# QRE1113_Digital_v10.net
KiCad netlist of a schematic drawn in EAGLE
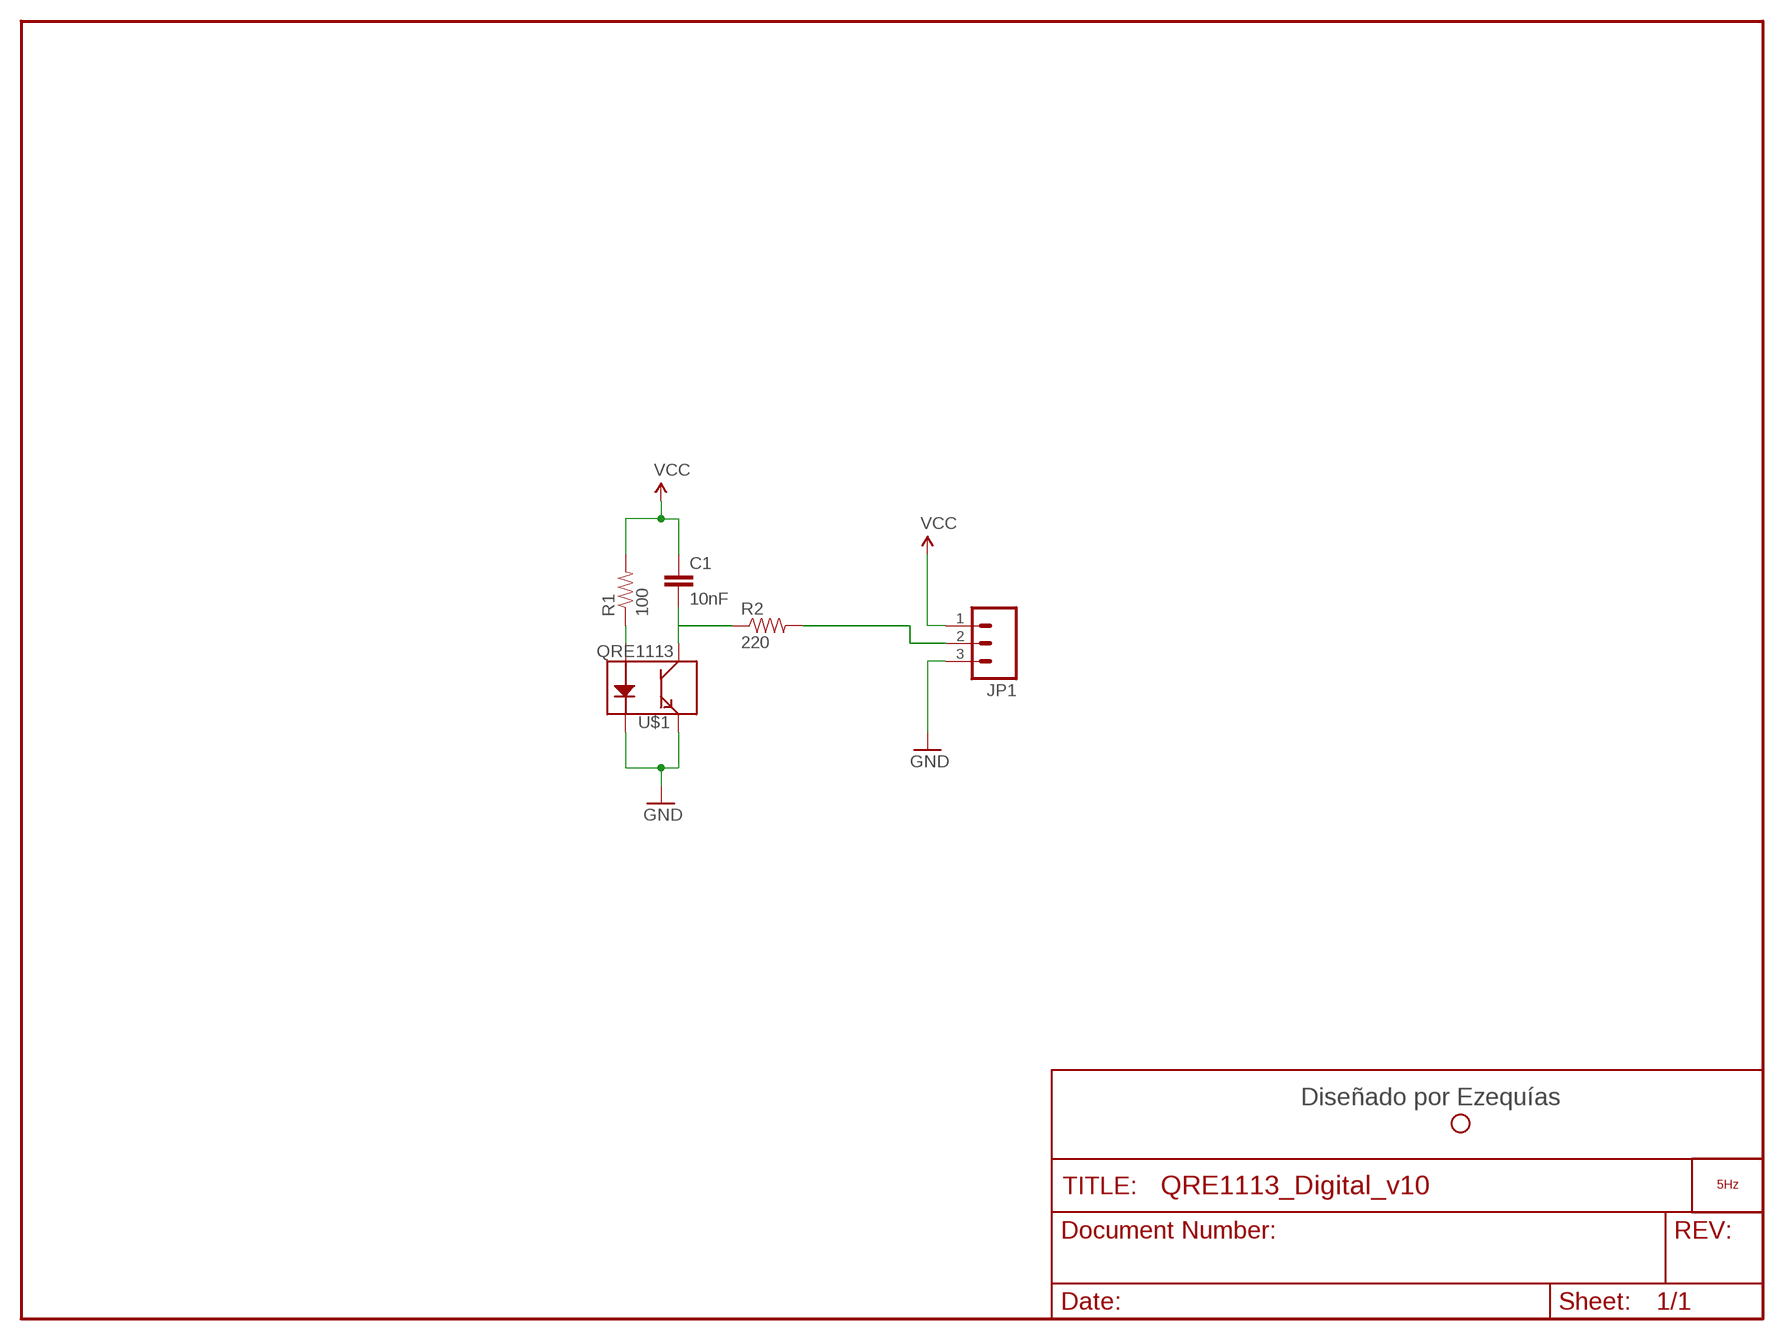
[diagram p0: schematic, sheet 1]

(export (version "E")
  (design (tool "Eeschema 10.0.6"))
  (components
    (comp (ref "C1")
      (value "10nF")
      (footprint "eagle-import:0603-CAP")
      (libsource (lib "eagle-import") (part "CAP0603-CAP"))
    )
    (comp (ref "JP1")
      (value "M03PTH")
      (footprint "eagle-import:1X03")
      (libsource (lib "eagle-import") (part "M03PTH"))
    )
    (comp (ref "JP2")
      (value "STAND-OFF")
      (footprint "eagle-import:STAND-OFF")
      (libsource (lib "eagle-import") (part "STAND-OFF"))
    )
    (comp (ref "LOGO1")
      (value "LOGO_5HZ_CIRC_5MM")
      (footprint "eagle-import:5HZ_LOGO_CIRC_5MM")
      (libsource (lib "eagle-import") (part "LOGO_5HZ_CIRC_5MM"))
    )
    (comp (ref "R1")
      (value "100")
      (footprint "eagle-import:0603-RES")
      (libsource (lib "eagle-import") (part "RESISTOR0603-RES"))
    )
    (comp (ref "R2")
      (value "220")
      (footprint "eagle-import:0603-RES")
      (libsource (lib "eagle-import") (part "RESISTOR0603-RES"))
    )
    (comp (ref "U$1")
      (value "QRE1113")
      (footprint "eagle-import:QRE1113")
      (libsource (lib "eagle-import") (part "QRE1113"))
    )
  )
  (nets
    (net (code "1") (name "GND") (class "Default")
      (node (ref "JP1") (pin "3") (pinfunction "3_3") (pintype "passive"))
      (node (ref "U$1") (pin "2") (pinfunction "K_2") (pintype "bidirectional"))
      (node (ref "U$1") (pin "4") (pinfunction "E_4") (pintype "bidirectional"))
    )
    (net (code "2") (name "Net-(JP1-Pad2)") (class "Default")
      (node (ref "JP1") (pin "2") (pinfunction "2_2") (pintype "passive"))
      (node (ref "R2") (pin "2") (pinfunction "2_2") (pintype "passive"))
    )
    (net (code "3") (name "Net-(U$1-A)") (class "Default")
      (node (ref "R1") (pin "1") (pinfunction "1_1") (pintype "passive"))
      (node (ref "U$1") (pin "1") (pinfunction "A_1") (pintype "bidirectional"))
    )
    (net (code "4") (name "Net-(U$1-C)") (class "Default")
      (node (ref "C1") (pin "2") (pinfunction "2_2") (pintype "passive"))
      (node (ref "R2") (pin "1") (pinfunction "1_1") (pintype "passive"))
      (node (ref "U$1") (pin "3") (pinfunction "C_3") (pintype "bidirectional"))
    )
    (net (code "5") (name "VCC") (class "Default")
      (node (ref "C1") (pin "1") (pinfunction "1_1") (pintype "passive"))
      (node (ref "JP1") (pin "1") (pinfunction "1_1") (pintype "passive"))
      (node (ref "R1") (pin "2") (pinfunction "2_2") (pintype "passive"))
    )
  )
)
